# Sheet1.net
KiCad netlist of a schematic drawn in Altium Designer
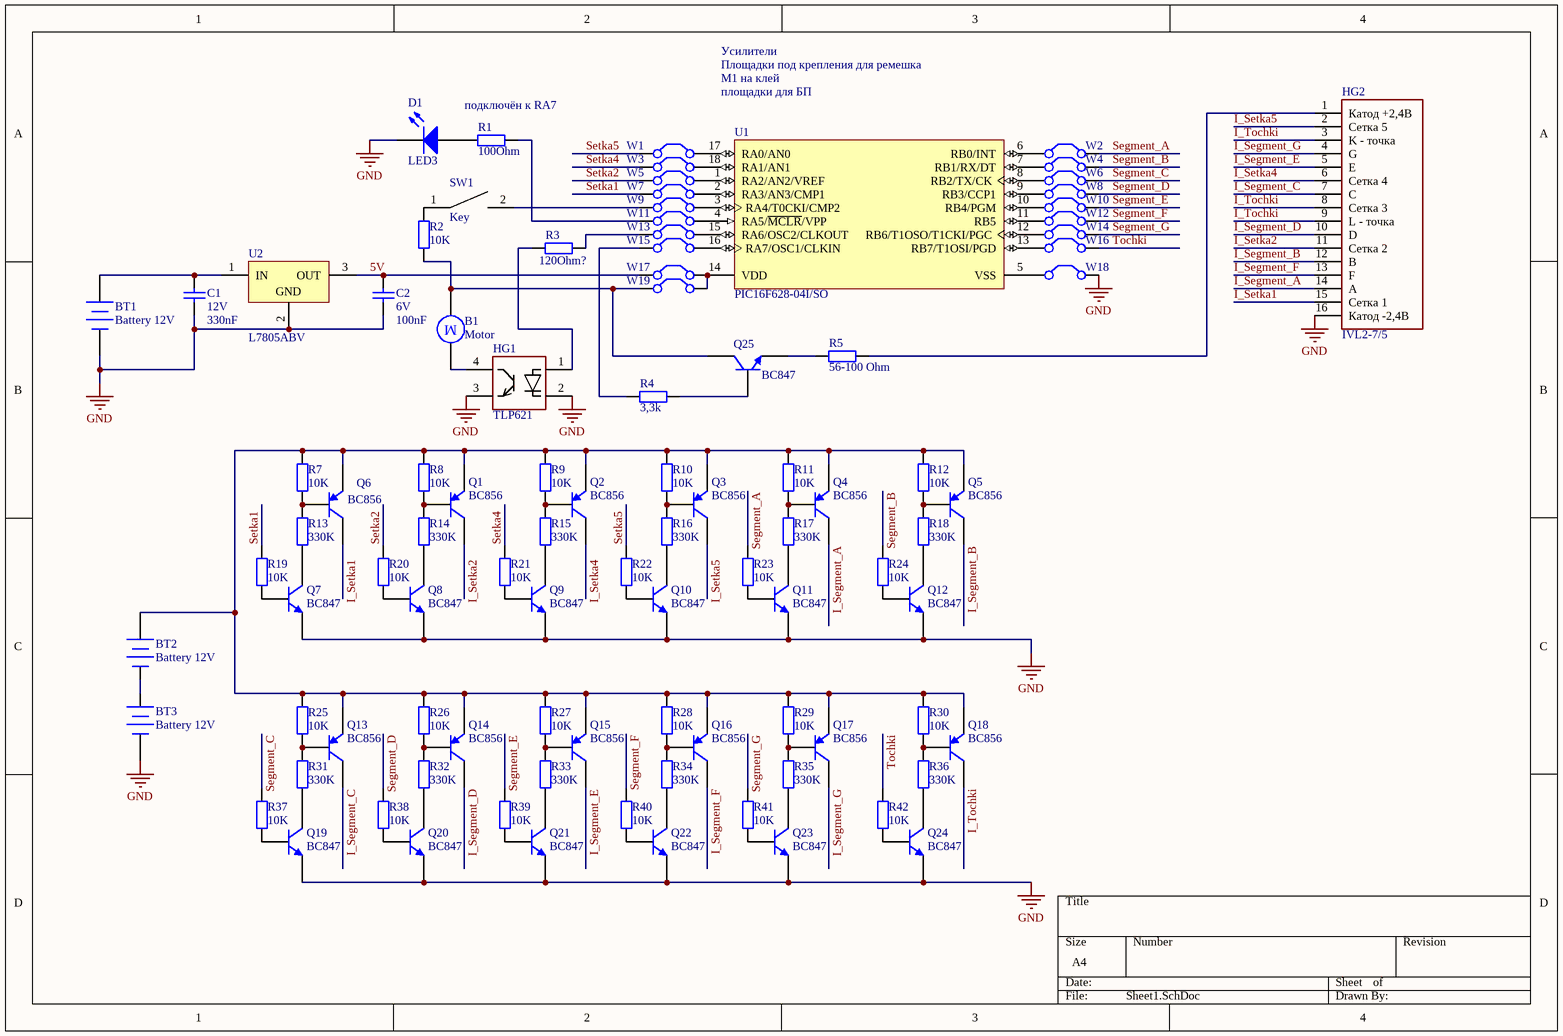
[diagram p0: Sheet1.SchDoc]

(export (version "E")
  (design (tool "Eeschema 10.0.6"))
  (components
    (comp (ref "B1")
      (value "Motor")
      (footprint "Motor")
      (description "Motor, General Kind")
      (fields (field (name "PUBLISHER") "Altium Limited"))
      (libsource (lib "Miscellaneous Devices") (part "Motor"))
    )
    (comp (ref "BT1")
      (value "Battery 12V")
      (footprint "BatteryA23")
      (description "Multicell Battery")
      (fields (field (name "PUBLISHER") "Altium Limited"))
      (libsource (lib "Miscellaneous Devices") (part "Battery"))
    )
    (comp (ref "BT2")
      (value "Battery 12V")
      (footprint "BatteryA23")
      (description "Multicell Battery")
      (fields (field (name "PUBLISHER") "Altium Limited"))
      (libsource (lib "Miscellaneous Devices") (part "Battery"))
    )
    (comp (ref "BT3")
      (value "Battery 12V")
      (footprint "PcbLib1:BatteryA23")
      (description "Multicell Battery")
      (fields (field (name "PUBLISHER") "Altium Limited"))
      (libsource (lib "Miscellaneous Devices") (part "Battery"))
    )
    (comp (ref "C1")
      (value "12V")
      (footprint "F1206")
      (description "Capacitor")
      (fields (field (name "ALTIUM_VALUE") "330nF") (field (name "PUBLISHER") "Altium Limited"))
      (libsource (lib "Miscellaneous Devices") (part "Cap"))
    )
    (comp (ref "C2")
      (value "6V")
      (footprint "F1206")
      (description "Capacitor")
      (fields (field (name "ALTIUM_VALUE") "100nF") (field (name "PUBLISHER") "Altium Limited"))
      (libsource (lib "Miscellaneous Devices") (part "Cap"))
    )
    (comp (ref "D1")
      (value "LED3")
      (footprint "F1206")
      (description "Typical BLUE SiC LED")
      (fields (field (name "PUBLISHER") "Altium Limited"))
      (libsource (lib "Miscellaneous Devices") (part "LED3"))
    )
    (comp (ref "HG1")
      (value "TLP621")
      (footprint "PcbLib1:Photocoupler")
      (libsource (lib "Schlib1") (part "Photocoupler"))
    )
    (comp (ref "HG2")
      (value "IVL2-7/5")
      (footprint "-IVL2-7/5")
      (libsource (lib "Schlib1") (part "IVL2-7/5"))
    )
    (comp (ref "Q1")
      (value "BC856")
      (footprint "SOT23_L")
      (description "PNP General-purpose Transistor")
      (fields (field (name "PUBLISHER") "Altium Limited"))
      (libsource (lib "Philips Discrete BJT - Low Power") (part "BC856"))
    )
    (comp (ref "Q2")
      (value "BC856")
      (footprint "SOT23_L")
      (description "PNP General-purpose Transistor")
      (fields (field (name "PUBLISHER") "Altium Limited"))
      (libsource (lib "Philips Discrete BJT - Low Power") (part "BC856"))
    )
    (comp (ref "Q3")
      (value "BC856")
      (footprint "SOT23_L")
      (description "PNP General-purpose Transistor")
      (fields (field (name "PUBLISHER") "Altium Limited"))
      (libsource (lib "Philips Discrete BJT - Low Power") (part "BC856"))
    )
    (comp (ref "Q4")
      (value "BC856")
      (footprint "SOT23_L")
      (description "PNP General-purpose Transistor")
      (fields (field (name "PUBLISHER") "Altium Limited"))
      (libsource (lib "Philips Discrete BJT - Low Power") (part "BC856"))
    )
    (comp (ref "Q5")
      (value "BC856")
      (footprint "SOT23_L")
      (description "PNP General-purpose Transistor")
      (fields (field (name "PUBLISHER") "Altium Limited"))
      (libsource (lib "Philips Discrete BJT - Low Power") (part "BC856"))
    )
    (comp (ref "Q6")
      (value "BC856")
      (footprint "SOT23_L")
      (description "PNP General-purpose Transistor")
      (fields (field (name "PUBLISHER") "Altium Limited"))
      (libsource (lib "Philips Discrete BJT - Low Power") (part "BC856"))
    )
    (comp (ref "Q7")
      (value "BC847")
      (footprint "SOT23_N")
      (description "NPN General-purpose Transistor")
      (fields (field (name "PUBLISHER") "Altium Limited"))
      (libsource (lib "Philips Discrete BJT - Low Power") (part "BC847"))
    )
    (comp (ref "Q8")
      (value "BC847")
      (footprint "SOT23_N")
      (description "NPN General-purpose Transistor")
      (fields (field (name "PUBLISHER") "Altium Limited"))
      (libsource (lib "Philips Discrete BJT - Low Power") (part "BC847"))
    )
    (comp (ref "Q9")
      (value "BC847")
      (footprint "SOT23_N")
      (description "NPN General-purpose Transistor")
      (fields (field (name "PUBLISHER") "Altium Limited"))
      (libsource (lib "Philips Discrete BJT - Low Power") (part "BC847"))
    )
    (comp (ref "Q10")
      (value "BC847")
      (footprint "SOT23_N")
      (description "NPN General-purpose Transistor")
      (fields (field (name "PUBLISHER") "Altium Limited"))
      (libsource (lib "Philips Discrete BJT - Low Power") (part "BC847"))
    )
    (comp (ref "Q11")
      (value "BC847")
      (footprint "SOT23_N")
      (description "NPN General-purpose Transistor")
      (fields (field (name "PUBLISHER") "Altium Limited"))
      (libsource (lib "Philips Discrete BJT - Low Power") (part "BC847"))
    )
    (comp (ref "Q12")
      (value "BC847")
      (footprint "SOT23_N")
      (description "NPN General-purpose Transistor")
      (fields (field (name "PUBLISHER") "Altium Limited"))
      (libsource (lib "Philips Discrete BJT - Low Power") (part "BC847"))
    )
    (comp (ref "Q13")
      (value "BC856")
      (footprint "SOT23_L")
      (description "PNP General-purpose Transistor")
      (fields (field (name "PUBLISHER") "Altium Limited"))
      (libsource (lib "Philips Discrete BJT - Low Power") (part "BC856"))
    )
    (comp (ref "Q14")
      (value "BC856")
      (footprint "SOT23_L")
      (description "PNP General-purpose Transistor")
      (fields (field (name "PUBLISHER") "Altium Limited"))
      (libsource (lib "Philips Discrete BJT - Low Power") (part "BC856"))
    )
    (comp (ref "Q15")
      (value "BC856")
      (footprint "SOT23_L")
      (description "PNP General-purpose Transistor")
      (fields (field (name "PUBLISHER") "Altium Limited"))
      (libsource (lib "Philips Discrete BJT - Low Power") (part "BC856"))
    )
    (comp (ref "Q16")
      (value "BC856")
      (footprint "SOT23_L")
      (description "PNP General-purpose Transistor")
      (fields (field (name "PUBLISHER") "Altium Limited"))
      (libsource (lib "Philips Discrete BJT - Low Power") (part "BC856"))
    )
    (comp (ref "Q17")
      (value "BC856")
      (footprint "SOT23_L")
      (description "PNP General-purpose Transistor")
      (fields (field (name "PUBLISHER") "Altium Limited"))
      (libsource (lib "Philips Discrete BJT - Low Power") (part "BC856"))
    )
    (comp (ref "Q18")
      (value "BC856")
      (footprint "SOT23_L")
      (description "PNP General-purpose Transistor")
      (fields (field (name "PUBLISHER") "Altium Limited"))
      (libsource (lib "Philips Discrete BJT - Low Power") (part "BC856"))
    )
    (comp (ref "Q19")
      (value "BC847")
      (footprint "SOT23_N")
      (description "NPN General-purpose Transistor")
      (fields (field (name "PUBLISHER") "Altium Limited"))
      (libsource (lib "Philips Discrete BJT - Low Power") (part "BC847"))
    )
    (comp (ref "Q20")
      (value "BC847")
      (footprint "SOT23_N")
      (description "NPN General-purpose Transistor")
      (fields (field (name "PUBLISHER") "Altium Limited"))
      (libsource (lib "Philips Discrete BJT - Low Power") (part "BC847"))
    )
    (comp (ref "Q21")
      (value "BC847")
      (footprint "SOT23_N")
      (description "NPN General-purpose Transistor")
      (fields (field (name "PUBLISHER") "Altium Limited"))
      (libsource (lib "Philips Discrete BJT - Low Power") (part "BC847"))
    )
    (comp (ref "Q22")
      (value "BC847")
      (footprint "SOT23_N")
      (description "NPN General-purpose Transistor")
      (fields (field (name "PUBLISHER") "Altium Limited"))
      (libsource (lib "Philips Discrete BJT - Low Power") (part "BC847"))
    )
    (comp (ref "Q23")
      (value "BC847")
      (footprint "SOT23_N")
      (description "NPN General-purpose Transistor")
      (fields (field (name "PUBLISHER") "Altium Limited"))
      (libsource (lib "Philips Discrete BJT - Low Power") (part "BC847"))
    )
    (comp (ref "Q24")
      (value "BC847")
      (footprint "SOT23_N")
      (description "NPN General-purpose Transistor")
      (fields (field (name "PUBLISHER") "Altium Limited"))
      (libsource (lib "Philips Discrete BJT - Low Power") (part "BC847"))
    )
    (comp (ref "Q25")
      (value "BC847")
      (footprint "SOT23_N")
      (description "NPN General-purpose Transistor")
      (fields (field (name "PUBLISHER") "Altium Limited"))
      (libsource (lib "Philips Discrete BJT - Low Power") (part "BC847"))
    )
    (comp (ref "R1")
      (value "100Ohm")
      (footprint "F1206")
      (description "Resistor")
      (fields (field (name "Comment") "Res2") (field (name "PUBLISHER") "Altium Limited"))
      (libsource (lib "") (part "Res2_3"))
    )
    (comp (ref "R2")
      (value "10K")
      (footprint "F1206")
      (description "Resistor")
      (fields (field (name "Comment") "Res2") (field (name "PUBLISHER") "Altium Limited"))
      (libsource (lib "Miscellaneous Devices") (part "Res2"))
    )
    (comp (ref "R3")
      (value "120Ohm?")
      (footprint "F1206")
      (description "Resistor")
      (fields (field (name "Comment") "Res2") (field (name "PUBLISHER") "Altium Limited"))
      (libsource (lib "") (part "Res2_3"))
    )
    (comp (ref "R4")
      (value "3,3k")
      (footprint "F1206")
      (description "Resistor")
      (fields (field (name "Comment") "Res2") (field (name "PUBLISHER") "Altium Limited"))
      (libsource (lib "") (part "Res2_3"))
    )
    (comp (ref "R5")
      (value "56-100 Ohm")
      (footprint "F1206")
      (description "Resistor")
      (fields (field (name "Comment") "Res2") (field (name "PUBLISHER") "Altium Limited"))
      (libsource (lib "") (part "Res2_2"))
    )
    (comp (ref "R7")
      (value "10K")
      (footprint "F0805")
      (description "Resistor")
      (fields (field (name "Comment") "Res2") (field (name "PUBLISHER") "Altium Limited"))
      (libsource (lib "Miscellaneous Devices") (part "Res2"))
    )
    (comp (ref "R8")
      (value "10K")
      (footprint "F0805")
      (description "Resistor")
      (fields (field (name "Comment") "Res2") (field (name "PUBLISHER") "Altium Limited"))
      (libsource (lib "Miscellaneous Devices") (part "Res2"))
    )
    (comp (ref "R9")
      (value "10K")
      (footprint "F0805")
      (description "Resistor")
      (fields (field (name "Comment") "Res2") (field (name "PUBLISHER") "Altium Limited"))
      (libsource (lib "Miscellaneous Devices") (part "Res2"))
    )
    (comp (ref "R10")
      (value "10K")
      (footprint "F0805")
      (description "Resistor")
      (fields (field (name "Comment") "Res2") (field (name "PUBLISHER") "Altium Limited"))
      (libsource (lib "Miscellaneous Devices") (part "Res2"))
    )
    (comp (ref "R11")
      (value "10K")
      (footprint "F0805")
      (description "Resistor")
      (fields (field (name "Comment") "Res2") (field (name "PUBLISHER") "Altium Limited"))
      (libsource (lib "Miscellaneous Devices") (part "Res2"))
    )
    (comp (ref "R12")
      (value "10K")
      (footprint "F0805")
      (description "Resistor")
      (fields (field (name "Comment") "Res2") (field (name "PUBLISHER") "Altium Limited"))
      (libsource (lib "Miscellaneous Devices") (part "Res2"))
    )
    (comp (ref "R13")
      (value "330K")
      (footprint "F1206")
      (description "Resistor")
      (fields (field (name "Comment") "Res2") (field (name "PUBLISHER") "Altium Limited"))
      (libsource (lib "Miscellaneous Devices") (part "Res2"))
    )
    (comp (ref "R14")
      (value "330K")
      (footprint "F1206")
      (description "Resistor")
      (fields (field (name "Comment") "Res2") (field (name "PUBLISHER") "Altium Limited"))
      (libsource (lib "Miscellaneous Devices") (part "Res2"))
    )
    (comp (ref "R15")
      (value "330K")
      (footprint "F1206")
      (description "Resistor")
      (fields (field (name "Comment") "Res2") (field (name "PUBLISHER") "Altium Limited"))
      (libsource (lib "Miscellaneous Devices") (part "Res2"))
    )
    (comp (ref "R16")
      (value "330K")
      (footprint "F1206")
      (description "Resistor")
      (fields (field (name "Comment") "Res2") (field (name "PUBLISHER") "Altium Limited"))
      (libsource (lib "Miscellaneous Devices") (part "Res2"))
    )
    (comp (ref "R17")
      (value "330K")
      (footprint "F1206")
      (description "Resistor")
      (fields (field (name "Comment") "Res2") (field (name "PUBLISHER") "Altium Limited"))
      (libsource (lib "Miscellaneous Devices") (part "Res2"))
    )
    (comp (ref "R18")
      (value "330K")
      (footprint "F1206")
      (description "Resistor")
      (fields (field (name "Comment") "Res2") (field (name "PUBLISHER") "Altium Limited"))
      (libsource (lib "Miscellaneous Devices") (part "Res2"))
    )
    (comp (ref "R19")
      (value "10K")
      (footprint "F1206")
      (description "Resistor")
      (fields (field (name "Comment") "Res2") (field (name "PUBLISHER") "Altium Limited"))
      (libsource (lib "") (part "Res2_1"))
    )
    (comp (ref "R20")
      (value "10K")
      (footprint "F1206")
      (description "Resistor")
      (fields (field (name "Comment") "Res2") (field (name "PUBLISHER") "Altium Limited"))
      (libsource (lib "") (part "Res2_1"))
    )
    (comp (ref "R21")
      (value "10K")
      (footprint "F1206")
      (description "Resistor")
      (fields (field (name "Comment") "Res2") (field (name "PUBLISHER") "Altium Limited"))
      (libsource (lib "") (part "Res2_1"))
    )
    (comp (ref "R22")
      (value "10K")
      (footprint "F1206")
      (description "Resistor")
      (fields (field (name "Comment") "Res2") (field (name "PUBLISHER") "Altium Limited"))
      (libsource (lib "") (part "Res2_1"))
    )
    (comp (ref "R23")
      (value "10K")
      (footprint "F1206")
      (description "Resistor")
      (fields (field (name "Comment") "Res2") (field (name "PUBLISHER") "Altium Limited"))
      (libsource (lib "") (part "Res2_1"))
    )
    (comp (ref "R24")
      (value "10K")
      (footprint "F1206")
      (description "Resistor")
      (fields (field (name "Comment") "Res2") (field (name "PUBLISHER") "Altium Limited"))
      (libsource (lib "") (part "Res2_1"))
    )
    (comp (ref "R25")
      (value "10K")
      (footprint "F0805")
      (description "Resistor")
      (fields (field (name "Comment") "Res2") (field (name "PUBLISHER") "Altium Limited"))
      (libsource (lib "Miscellaneous Devices") (part "Res2"))
    )
    (comp (ref "R26")
      (value "10K")
      (footprint "F0805")
      (description "Resistor")
      (fields (field (name "Comment") "Res2") (field (name "PUBLISHER") "Altium Limited"))
      (libsource (lib "Miscellaneous Devices") (part "Res2"))
    )
    (comp (ref "R27")
      (value "10K")
      (footprint "F0805")
      (description "Resistor")
      (fields (field (name "Comment") "Res2") (field (name "PUBLISHER") "Altium Limited"))
      (libsource (lib "Miscellaneous Devices") (part "Res2"))
    )
    (comp (ref "R28")
      (value "10K")
      (footprint "F0805")
      (description "Resistor")
      (fields (field (name "Comment") "Res2") (field (name "PUBLISHER") "Altium Limited"))
      (libsource (lib "Miscellaneous Devices") (part "Res2"))
    )
    (comp (ref "R29")
      (value "10K")
      (footprint "F0805")
      (description "Resistor")
      (fields (field (name "Comment") "Res2") (field (name "PUBLISHER") "Altium Limited"))
      (libsource (lib "Miscellaneous Devices") (part "Res2"))
    )
    (comp (ref "R30")
      (value "10K")
      (footprint "F0805")
      (description "Resistor")
      (fields (field (name "Comment") "Res2") (field (name "PUBLISHER") "Altium Limited"))
      (libsource (lib "Miscellaneous Devices") (part "Res2"))
    )
    (comp (ref "R31")
      (value "330K")
      (footprint "F1206")
      (description "Resistor")
      (fields (field (name "Comment") "Res2") (field (name "PUBLISHER") "Altium Limited"))
      (libsource (lib "Miscellaneous Devices") (part "Res2"))
    )
    (comp (ref "R32")
      (value "330K")
      (footprint "F1206")
      (description "Resistor")
      (fields (field (name "Comment") "Res2") (field (name "PUBLISHER") "Altium Limited"))
      (libsource (lib "Miscellaneous Devices") (part "Res2"))
    )
    (comp (ref "R33")
      (value "330K")
      (footprint "F1206")
      (description "Resistor")
      (fields (field (name "Comment") "Res2") (field (name "PUBLISHER") "Altium Limited"))
      (libsource (lib "Miscellaneous Devices") (part "Res2"))
    )
    (comp (ref "R34")
      (value "330K")
      (footprint "F1206")
      (description "Resistor")
      (fields (field (name "Comment") "Res2") (field (name "PUBLISHER") "Altium Limited"))
      (libsource (lib "Miscellaneous Devices") (part "Res2"))
    )
    (comp (ref "R35")
      (value "330K")
      (footprint "F1206")
      (description "Resistor")
      (fields (field (name "Comment") "Res2") (field (name "PUBLISHER") "Altium Limited"))
      (libsource (lib "Miscellaneous Devices") (part "Res2"))
    )
    (comp (ref "R36")
      (value "330K")
      (footprint "F1206")
      (description "Resistor")
      (fields (field (name "Comment") "Res2") (field (name "PUBLISHER") "Altium Limited"))
      (libsource (lib "Miscellaneous Devices") (part "Res2"))
    )
    (comp (ref "R37")
      (value "10K")
      (footprint "F1206")
      (description "Resistor")
      (fields (field (name "Comment") "Res2") (field (name "PUBLISHER") "Altium Limited"))
      (libsource (lib "") (part "Res2_1"))
    )
    (comp (ref "R38")
      (value "10K")
      (footprint "F1206")
      (description "Resistor")
      (fields (field (name "Comment") "Res2") (field (name "PUBLISHER") "Altium Limited"))
      (libsource (lib "") (part "Res2_1"))
    )
    (comp (ref "R39")
      (value "10K")
      (footprint "F1206")
      (description "Resistor")
      (fields (field (name "Comment") "Res2") (field (name "PUBLISHER") "Altium Limited"))
      (libsource (lib "") (part "Res2_1"))
    )
    (comp (ref "R40")
      (value "10K")
      (footprint "F1206")
      (description "Resistor")
      (fields (field (name "Comment") "Res2") (field (name "PUBLISHER") "Altium Limited"))
      (libsource (lib "") (part "Res2_1"))
    )
    (comp (ref "R41")
      (value "10K")
      (footprint "F1206")
      (description "Resistor")
      (fields (field (name "Comment") "Res2") (field (name "PUBLISHER") "Altium Limited"))
      (libsource (lib "") (part "Res2_1"))
    )
    (comp (ref "R42")
      (value "10K")
      (footprint "F1206")
      (description "Resistor")
      (fields (field (name "Comment") "Res2") (field (name "PUBLISHER") "Altium Limited"))
      (libsource (lib "") (part "Res2_1"))
    )
    (comp (ref "SW1") (value "Key") (footprint "Button") (libsource (lib "Schlib1") (part "SW")))
    (comp (ref "U1")
      (value "PIC16F628-04I/SO")
      (footprint "MCHP-SOIC-SO18_N")
      (description "Flash-Based 8-Bit CMOS Microcontroller, 4 MHz, 16 I/O, -40 to 85 degC, 18-pin SOIC (SO18), Tube")
      (fields (field (name "MANUFACTURER") "Microchip"))
      (libsource (lib "Microchip PIC16 Part 1") (part "PIC16F628-04I/SO"))
    )
    (comp (ref "U2")
      (value "L7805ABV")
      (footprint "KREN")
      (description "Positive Voltage Regulator, 5V, 3-Pin TO-220")
      (libsource (lib "STMicroelectronics Power Management Linear Regulator") (part "L7805ABV"))
    )
    (comp (ref "W1")
      (value "Jumper")
      (footprint "перемычка")
      (description "Jumper Wire")
      (fields (field (name "PUBLISHER") "Altium Limited"))
      (libsource (lib "Miscellaneous Devices") (part "Jumper"))
    )
    (comp (ref "W2")
      (value "Jumper")
      (footprint "перемычка")
      (description "Jumper Wire")
      (fields (field (name "PUBLISHER") "Altium Limited"))
      (libsource (lib "Miscellaneous Devices") (part "Jumper"))
    )
    (comp (ref "W3")
      (value "Jumper")
      (footprint "перемычка")
      (description "Jumper Wire")
      (fields (field (name "PUBLISHER") "Altium Limited"))
      (libsource (lib "Miscellaneous Devices") (part "Jumper"))
    )
    (comp (ref "W4")
      (value "Jumper")
      (footprint "перемычка")
      (description "Jumper Wire")
      (fields (field (name "PUBLISHER") "Altium Limited"))
      (libsource (lib "Miscellaneous Devices") (part "Jumper"))
    )
    (comp (ref "W5")
      (value "Jumper")
      (footprint "перемычка")
      (description "Jumper Wire")
      (fields (field (name "PUBLISHER") "Altium Limited"))
      (libsource (lib "Miscellaneous Devices") (part "Jumper"))
    )
    (comp (ref "W6")
      (value "Jumper")
      (footprint "перемычка")
      (description "Jumper Wire")
      (fields (field (name "PUBLISHER") "Altium Limited"))
      (libsource (lib "Miscellaneous Devices") (part "Jumper"))
    )
    (comp (ref "W7")
      (value "Jumper")
      (footprint "перемычка")
      (description "Jumper Wire")
      (fields (field (name "PUBLISHER") "Altium Limited"))
      (libsource (lib "Miscellaneous Devices") (part "Jumper"))
    )
    (comp (ref "W8")
      (value "Jumper")
      (footprint "перемычка")
      (description "Jumper Wire")
      (fields (field (name "PUBLISHER") "Altium Limited"))
      (libsource (lib "Miscellaneous Devices") (part "Jumper"))
    )
    (comp (ref "W9")
      (value "Jumper")
      (footprint "перемычка")
      (description "Jumper Wire")
      (fields (field (name "PUBLISHER") "Altium Limited"))
      (libsource (lib "Miscellaneous Devices") (part "Jumper"))
    )
    (comp (ref "W10")
      (value "Jumper")
      (footprint "перемычка")
      (description "Jumper Wire")
      (fields (field (name "PUBLISHER") "Altium Limited"))
      (libsource (lib "Miscellaneous Devices") (part "Jumper"))
    )
    (comp (ref "W11")
      (value "Jumper")
      (footprint "перемычка")
      (description "Jumper Wire")
      (fields (field (name "PUBLISHER") "Altium Limited"))
      (libsource (lib "Miscellaneous Devices") (part "Jumper"))
    )
    (comp (ref "W12")
      (value "Jumper")
      (footprint "перемычка")
      (description "Jumper Wire")
      (fields (field (name "PUBLISHER") "Altium Limited"))
      (libsource (lib "Miscellaneous Devices") (part "Jumper"))
    )
    (comp (ref "W13")
      (value "Jumper")
      (footprint "перемычка")
      (description "Jumper Wire")
      (fields (field (name "PUBLISHER") "Altium Limited"))
      (libsource (lib "Miscellaneous Devices") (part "Jumper"))
    )
    (comp (ref "W14")
      (value "Jumper")
      (footprint "перемычка")
      (description "Jumper Wire")
      (fields (field (name "PUBLISHER") "Altium Limited"))
      (libsource (lib "Miscellaneous Devices") (part "Jumper"))
    )
    (comp (ref "W15")
      (value "Jumper")
      (footprint "перемычка")
      (description "Jumper Wire")
      (fields (field (name "PUBLISHER") "Altium Limited"))
      (libsource (lib "Miscellaneous Devices") (part "Jumper"))
    )
    (comp (ref "W16")
      (value "Jumper")
      (footprint "перемычка")
      (description "Jumper Wire")
      (fields (field (name "PUBLISHER") "Altium Limited"))
      (libsource (lib "Miscellaneous Devices") (part "Jumper"))
    )
    (comp (ref "W17")
      (value "Jumper")
      (footprint "перемычка")
      (description "Jumper Wire")
      (fields (field (name "PUBLISHER") "Altium Limited"))
      (libsource (lib "Miscellaneous Devices") (part "Jumper"))
    )
    (comp (ref "W18")
      (value "Jumper")
      (footprint "перемычка")
      (description "Jumper Wire")
      (fields (field (name "PUBLISHER") "Altium Limited"))
      (libsource (lib "Miscellaneous Devices") (part "Jumper"))
    )
    (comp (ref "W19")
      (value "Jumper")
      (footprint "перемычка")
      (description "Jumper Wire")
      (fields (field (name "PUBLISHER") "Altium Limited"))
      (libsource (lib "Miscellaneous Devices") (part "Jumper"))
    )
  )
  (nets
    (net (code "1") (name "/5V") (class "Default")
      (node (ref "C2") (pin "1") (pinfunction "1_1") (pintype "passive"))
      (node (ref "U2") (pin "3") (pinfunction "OUT_3") (pintype "power_in"))
      (node (ref "W17") (pin "1") (pinfunction "C1_1") (pintype "passive"))
    )
    (net (code "2") (name "/I_Segment_A") (class "Default")
      (node (ref "HG2") (pin "14") (pinfunction "A_14") (pintype "passive"))
      (node (ref "Q4") (pin "3") (pinfunction "C_3") (pintype "passive"))
    )
    (net (code "3") (name "/I_Segment_B") (class "Default")
      (node (ref "HG2") (pin "12") (pinfunction "B_12") (pintype "passive"))
      (node (ref "Q5") (pin "3") (pinfunction "C_3") (pintype "passive"))
    )
    (net (code "4") (name "/I_Segment_C") (class "Default")
      (node (ref "HG2") (pin "7") (pinfunction "C_7") (pintype "passive"))
      (node (ref "Q13") (pin "3") (pinfunction "C_3") (pintype "passive"))
    )
    (net (code "5") (name "/I_Segment_D") (class "Default")
      (node (ref "HG2") (pin "10") (pinfunction "D_10") (pintype "passive"))
      (node (ref "Q14") (pin "3") (pinfunction "C_3") (pintype "passive"))
    )
    (net (code "6") (name "/I_Segment_E") (class "Default")
      (node (ref "HG2") (pin "5") (pinfunction "E_5") (pintype "passive"))
      (node (ref "Q15") (pin "3") (pinfunction "C_3") (pintype "passive"))
    )
    (net (code "7") (name "/I_Segment_F") (class "Default")
      (node (ref "HG2") (pin "13") (pinfunction "F_13") (pintype "passive"))
      (node (ref "Q16") (pin "3") (pinfunction "C_3") (pintype "passive"))
    )
    (net (code "8") (name "/I_Segment_G") (class "Default")
      (node (ref "HG2") (pin "4") (pinfunction "G_4") (pintype "passive"))
      (node (ref "Q17") (pin "3") (pinfunction "C_3") (pintype "passive"))
    )
    (net (code "9") (name "/I_Setka1") (class "Default")
      (node (ref "HG2") (pin "15") (pinfunction "Сетка_1_15") (pintype "passive"))
      (node (ref "Q6") (pin "3") (pinfunction "C_3") (pintype "passive"))
    )
    (net (code "10") (name "/I_Setka2") (class "Default")
      (node (ref "HG2") (pin "11") (pinfunction "Сетка_2_11") (pintype "passive"))
      (node (ref "Q1") (pin "3") (pinfunction "C_3") (pintype "passive"))
    )
    (net (code "11") (name "/I_Setka4") (class "Default")
      (node (ref "HG2") (pin "6") (pinfunction "Сетка_4_6") (pintype "passive"))
      (node (ref "Q2") (pin "3") (pinfunction "C_3") (pintype "passive"))
    )
    (net (code "12") (name "/I_Setka5") (class "Default")
      (node (ref "HG2") (pin "2") (pinfunction "Сетка_5_2") (pintype "passive"))
      (node (ref "Q3") (pin "3") (pinfunction "C_3") (pintype "passive"))
    )
    (net (code "13") (name "/I_Tochki") (class "Default")
      (node (ref "HG2") (pin "3") (pinfunction "K_-_точка_3") (pintype "passive"))
      (node (ref "HG2") (pin "8") (pinfunction "Сетка_3_8") (pintype "passive"))
      (node (ref "HG2") (pin "9") (pinfunction "L_-_точка_9") (pintype "passive"))
      (node (ref "Q18") (pin "3") (pinfunction "C_3") (pintype "passive"))
    )
    (net (code "14") (name "/Segment_A") (class "Default")
      (node (ref "R23") (pin "1") (pinfunction "1_1") (pintype "passive"))
      (node (ref "W2") (pin "2") (pinfunction "C2_2") (pintype "passive"))
    )
    (net (code "15") (name "/Segment_B") (class "Default")
      (node (ref "R24") (pin "1") (pinfunction "1_1") (pintype "passive"))
      (node (ref "W4") (pin "2") (pinfunction "C2_2") (pintype "passive"))
    )
    (net (code "16") (name "/Segment_C") (class "Default")
      (node (ref "R37") (pin "1") (pinfunction "1_1") (pintype "passive"))
      (node (ref "W6") (pin "2") (pinfunction "C2_2") (pintype "passive"))
    )
    (net (code "17") (name "/Segment_D") (class "Default")
      (node (ref "R38") (pin "1") (pinfunction "1_1") (pintype "passive"))
      (node (ref "W8") (pin "2") (pinfunction "C2_2") (pintype "passive"))
    )
    (net (code "18") (name "/Segment_E") (class "Default")
      (node (ref "R39") (pin "1") (pinfunction "1_1") (pintype "passive"))
      (node (ref "W10") (pin "2") (pinfunction "C2_2") (pintype "passive"))
    )
    (net (code "19") (name "/Segment_F") (class "Default")
      (node (ref "R40") (pin "1") (pinfunction "1_1") (pintype "passive"))
      (node (ref "W12") (pin "2") (pinfunction "C2_2") (pintype "passive"))
    )
    (net (code "20") (name "/Segment_G") (class "Default")
      (node (ref "R41") (pin "1") (pinfunction "1_1") (pintype "passive"))
      (node (ref "W14") (pin "2") (pinfunction "C2_2") (pintype "passive"))
    )
    (net (code "21") (name "/Setka1") (class "Default")
      (node (ref "R19") (pin "1") (pinfunction "1_1") (pintype "passive"))
      (node (ref "W7") (pin "1") (pinfunction "C1_1") (pintype "passive"))
    )
    (net (code "22") (name "/Setka2") (class "Default")
      (node (ref "R20") (pin "1") (pinfunction "1_1") (pintype "passive"))
      (node (ref "W5") (pin "1") (pinfunction "C1_1") (pintype "passive"))
    )
    (net (code "23") (name "/Setka4") (class "Default")
      (node (ref "R21") (pin "1") (pinfunction "1_1") (pintype "passive"))
      (node (ref "W3") (pin "1") (pinfunction "C1_1") (pintype "passive"))
    )
    (net (code "24") (name "/Setka5") (class "Default")
      (node (ref "R22") (pin "1") (pinfunction "1_1") (pintype "passive"))
      (node (ref "W1") (pin "1") (pinfunction "C1_1") (pintype "passive"))
    )
    (net (code "25") (name "/Tochki") (class "Default")
      (node (ref "R42") (pin "1") (pinfunction "1_1") (pintype "passive"))
      (node (ref "W16") (pin "2") (pinfunction "C2_2") (pintype "passive"))
    )
    (net (code "26") (name "GND") (class "Default")
      (node (ref "BT1") (pin "2") (pinfunction "-_2") (pintype "passive"))
      (node (ref "BT3") (pin "2") (pinfunction "-_2") (pintype "passive"))
      (node (ref "C1") (pin "1") (pinfunction "1_1") (pintype "passive"))
      (node (ref "C2") (pin "2") (pinfunction "2_2") (pintype "passive"))
      (node (ref "D1") (pin "2") (pinfunction "K_2") (pintype "passive"))
      (node (ref "HG1") (pin "2") (pinfunction "2_2") (pintype "passive"))
      (node (ref "HG1") (pin "3") (pinfunction "3_3") (pintype "passive"))
      (node (ref "HG2") (pin "16") (pinfunction "Катод_-2,4В_16") (pintype "passive"))
      (node (ref "Q10") (pin "2") (pinfunction "E_2") (pintype "passive"))
      (node (ref "Q11") (pin "2") (pinfunction "E_2") (pintype "passive"))
      (node (ref "Q12") (pin "2") (pinfunction "E_2") (pintype "passive"))
      (node (ref "Q19") (pin "2") (pinfunction "E_2") (pintype "passive"))
      (node (ref "Q20") (pin "2") (pinfunction "E_2") (pintype "passive"))
      (node (ref "Q21") (pin "2") (pinfunction "E_2") (pintype "passive"))
      (node (ref "Q22") (pin "2") (pinfunction "E_2") (pintype "passive"))
      (node (ref "Q23") (pin "2") (pinfunction "E_2") (pintype "passive"))
      (node (ref "Q24") (pin "2") (pinfunction "E_2") (pintype "passive"))
      (node (ref "Q7") (pin "2") (pinfunction "E_2") (pintype "passive"))
      (node (ref "Q8") (pin "2") (pinfunction "E_2") (pintype "passive"))
      (node (ref "Q9") (pin "2") (pinfunction "E_2") (pintype "passive"))
      (node (ref "U2") (pin "2") (pinfunction "GND_2") (pintype "power_in"))
      (node (ref "W18") (pin "2") (pinfunction "C2_2") (pintype "passive"))
    )
    (net (code "27") (name "Net-(B1-Pad1)") (class "Default")
      (node (ref "B1") (pin "1") (pinfunction "1_1") (pintype "passive"))
      (node (ref "HG1") (pin "4") (pinfunction "4_4") (pintype "passive"))
    )
    (net (code "28") (name "Net-(BT1-+)") (class "Default")
      (node (ref "BT1") (pin "1") (pinfunction "+_1") (pintype "passive"))
      (node (ref "C1") (pin "2") (pinfunction "2_2") (pintype "passive"))
      (node (ref "U2") (pin "1") (pinfunction "IN_1") (pintype "power_in"))
    )
    (net (code "29") (name "Net-(BT2-+)") (class "Default")
      (node (ref "BT2") (pin "1") (pinfunction "+_1") (pintype "passive"))
      (node (ref "Q1") (pin "2") (pinfunction "E_2") (pintype "passive"))
      (node (ref "Q13") (pin "2") (pinfunction "E_2") (pintype "passive"))
      (node (ref "Q14") (pin "2") (pinfunction "E_2") (pintype "passive"))
      (node (ref "Q15") (pin "2") (pinfunction "E_2") (pintype "passive"))
      (node (ref "Q16") (pin "2") (pinfunction "E_2") (pintype "passive"))
      (node (ref "Q17") (pin "2") (pinfunction "E_2") (pintype "passive"))
      (node (ref "Q18") (pin "2") (pinfunction "E_2") (pintype "passive"))
      (node (ref "Q2") (pin "2") (pinfunction "E_2") (pintype "passive"))
      (node (ref "Q3") (pin "2") (pinfunction "E_2") (pintype "passive"))
      (node (ref "Q4") (pin "2") (pinfunction "E_2") (pintype "passive"))
      (node (ref "Q5") (pin "2") (pinfunction "E_2") (pintype "passive"))
      (node (ref "Q6") (pin "2") (pinfunction "E_2") (pintype "passive"))
      (node (ref "R10") (pin "2") (pinfunction "2_2") (pintype "passive"))
      (node (ref "R11") (pin "2") (pinfunction "2_2") (pintype "passive"))
      (node (ref "R12") (pin "2") (pinfunction "2_2") (pintype "passive"))
      (node (ref "R25") (pin "2") (pinfunction "2_2") (pintype "passive"))
      (node (ref "R26") (pin "2") (pinfunction "2_2") (pintype "passive"))
      (node (ref "R27") (pin "2") (pinfunction "2_2") (pintype "passive"))
      (node (ref "R28") (pin "2") (pinfunction "2_2") (pintype "passive"))
      (node (ref "R29") (pin "2") (pinfunction "2_2") (pintype "passive"))
      (node (ref "R30") (pin "2") (pinfunction "2_2") (pintype "passive"))
      (node (ref "R7") (pin "2") (pinfunction "2_2") (pintype "passive"))
      (node (ref "R8") (pin "2") (pinfunction "2_2") (pintype "passive"))
      (node (ref "R9") (pin "2") (pinfunction "2_2") (pintype "passive"))
    )
    (net (code "30") (name "Net-(BT2--)") (class "Default")
      (node (ref "BT2") (pin "2") (pinfunction "-_2") (pintype "passive"))
      (node (ref "BT3") (pin "1") (pinfunction "+_1") (pintype "passive"))
    )
    (net (code "31") (name "Net-(D1-A)") (class "Default")
      (node (ref "D1") (pin "1") (pinfunction "A_1") (pintype "passive"))
      (node (ref "R1") (pin "1") (pinfunction "1_1") (pintype "passive"))
    )
    (net (code "32") (name "Net-(HG1-Pad1)") (class "Default")
      (node (ref "HG1") (pin "1") (pinfunction "1_1") (pintype "passive"))
      (node (ref "R3") (pin "1") (pinfunction "1_1") (pintype "passive"))
    )
    (net (code "33") (name "Net-(HG2-Катод_+2,4В)") (class "Default")
      (node (ref "HG2") (pin "1") (pinfunction "Катод_+2,4В_1") (pintype "passive"))
      (node (ref "R5") (pin "1") (pinfunction "1_1") (pintype "passive"))
    )
    (net (code "34") (name "Net-(Q1-B)") (class "Default")
      (node (ref "Q1") (pin "1") (pinfunction "B_1") (pintype "passive"))
      (node (ref "R14") (pin "2") (pinfunction "2_2") (pintype "passive"))
      (node (ref "R8") (pin "1") (pinfunction "1_1") (pintype "passive"))
    )
    (net (code "35") (name "Net-(Q2-B)") (class "Default")
      (node (ref "Q2") (pin "1") (pinfunction "B_1") (pintype "passive"))
      (node (ref "R15") (pin "2") (pinfunction "2_2") (pintype "passive"))
      (node (ref "R9") (pin "1") (pinfunction "1_1") (pintype "passive"))
    )
    (net (code "36") (name "Net-(Q3-B)") (class "Default")
      (node (ref "Q3") (pin "1") (pinfunction "B_1") (pintype "passive"))
      (node (ref "R10") (pin "1") (pinfunction "1_1") (pintype "passive"))
      (node (ref "R16") (pin "2") (pinfunction "2_2") (pintype "passive"))
    )
    (net (code "37") (name "Net-(Q4-B)") (class "Default")
      (node (ref "Q4") (pin "1") (pinfunction "B_1") (pintype "passive"))
      (node (ref "R11") (pin "1") (pinfunction "1_1") (pintype "passive"))
      (node (ref "R17") (pin "2") (pinfunction "2_2") (pintype "passive"))
    )
    (net (code "38") (name "Net-(Q5-B)") (class "Default")
      (node (ref "Q5") (pin "1") (pinfunction "B_1") (pintype "passive"))
      (node (ref "R12") (pin "1") (pinfunction "1_1") (pintype "passive"))
      (node (ref "R18") (pin "2") (pinfunction "2_2") (pintype "passive"))
    )
    (net (code "39") (name "Net-(Q6-B)") (class "Default")
      (node (ref "Q6") (pin "1") (pinfunction "B_1") (pintype "passive"))
      (node (ref "R13") (pin "2") (pinfunction "2_2") (pintype "passive"))
      (node (ref "R7") (pin "1") (pinfunction "1_1") (pintype "passive"))
    )
    (net (code "40") (name "Net-(Q7-B)") (class "Default")
      (node (ref "Q7") (pin "1") (pinfunction "B_1") (pintype "passive"))
      (node (ref "R19") (pin "2") (pinfunction "2_2") (pintype "passive"))
    )
    (net (code "41") (name "Net-(Q7-C)") (class "Default")
      (node (ref "Q7") (pin "3") (pinfunction "C_3") (pintype "passive"))
      (node (ref "R13") (pin "1") (pinfunction "1_1") (pintype "passive"))
    )
    (net (code "42") (name "Net-(Q8-B)") (class "Default")
      (node (ref "Q8") (pin "1") (pinfunction "B_1") (pintype "passive"))
      (node (ref "R20") (pin "2") (pinfunction "2_2") (pintype "passive"))
    )
    (net (code "43") (name "Net-(Q8-C)") (class "Default")
      (node (ref "Q8") (pin "3") (pinfunction "C_3") (pintype "passive"))
      (node (ref "R14") (pin "1") (pinfunction "1_1") (pintype "passive"))
    )
    (net (code "44") (name "Net-(Q9-B)") (class "Default")
      (node (ref "Q9") (pin "1") (pinfunction "B_1") (pintype "passive"))
      (node (ref "R21") (pin "2") (pinfunction "2_2") (pintype "passive"))
    )
    (net (code "45") (name "Net-(Q9-C)") (class "Default")
      (node (ref "Q9") (pin "3") (pinfunction "C_3") (pintype "passive"))
      (node (ref "R15") (pin "1") (pinfunction "1_1") (pintype "passive"))
    )
    (net (code "46") (name "Net-(Q10-B)") (class "Default")
      (node (ref "Q10") (pin "1") (pinfunction "B_1") (pintype "passive"))
      (node (ref "R22") (pin "2") (pinfunction "2_2") (pintype "passive"))
    )
    (net (code "47") (name "Net-(Q10-C)") (class "Default")
      (node (ref "Q10") (pin "3") (pinfunction "C_3") (pintype "passive"))
      (node (ref "R16") (pin "1") (pinfunction "1_1") (pintype "passive"))
    )
    (net (code "48") (name "Net-(Q11-B)") (class "Default")
      (node (ref "Q11") (pin "1") (pinfunction "B_1") (pintype "passive"))
      (node (ref "R23") (pin "2") (pinfunction "2_2") (pintype "passive"))
    )
    (net (code "49") (name "Net-(Q11-C)") (class "Default")
      (node (ref "Q11") (pin "3") (pinfunction "C_3") (pintype "passive"))
      (node (ref "R17") (pin "1") (pinfunction "1_1") (pintype "passive"))
    )
    (net (code "50") (name "Net-(Q12-B)") (class "Default")
      (node (ref "Q12") (pin "1") (pinfunction "B_1") (pintype "passive"))
      (node (ref "R24") (pin "2") (pinfunction "2_2") (pintype "passive"))
    )
    (net (code "51") (name "Net-(Q12-C)") (class "Default")
      (node (ref "Q12") (pin "3") (pinfunction "C_3") (pintype "passive"))
      (node (ref "R18") (pin "1") (pinfunction "1_1") (pintype "passive"))
    )
    (net (code "52") (name "Net-(Q13-B)") (class "Default")
      (node (ref "Q13") (pin "1") (pinfunction "B_1") (pintype "passive"))
      (node (ref "R25") (pin "1") (pinfunction "1_1") (pintype "passive"))
      (node (ref "R31") (pin "2") (pinfunction "2_2") (pintype "passive"))
    )
    (net (code "53") (name "Net-(Q14-B)") (class "Default")
      (node (ref "Q14") (pin "1") (pinfunction "B_1") (pintype "passive"))
      (node (ref "R26") (pin "1") (pinfunction "1_1") (pintype "passive"))
      (node (ref "R32") (pin "2") (pinfunction "2_2") (pintype "passive"))
    )
    (net (code "54") (name "Net-(Q15-B)") (class "Default")
      (node (ref "Q15") (pin "1") (pinfunction "B_1") (pintype "passive"))
      (node (ref "R27") (pin "1") (pinfunction "1_1") (pintype "passive"))
      (node (ref "R33") (pin "2") (pinfunction "2_2") (pintype "passive"))
    )
    (net (code "55") (name "Net-(Q16-B)") (class "Default")
      (node (ref "Q16") (pin "1") (pinfunction "B_1") (pintype "passive"))
      (node (ref "R28") (pin "1") (pinfunction "1_1") (pintype "passive"))
      (node (ref "R34") (pin "2") (pinfunction "2_2") (pintype "passive"))
    )
    (net (code "56") (name "Net-(Q17-B)") (class "Default")
      (node (ref "Q17") (pin "1") (pinfunction "B_1") (pintype "passive"))
      (node (ref "R29") (pin "1") (pinfunction "1_1") (pintype "passive"))
      (node (ref "R35") (pin "2") (pinfunction "2_2") (pintype "passive"))
    )
    (net (code "57") (name "Net-(Q18-B)") (class "Default")
      (node (ref "Q18") (pin "1") (pinfunction "B_1") (pintype "passive"))
      (node (ref "R30") (pin "1") (pinfunction "1_1") (pintype "passive"))
      (node (ref "R36") (pin "2") (pinfunction "2_2") (pintype "passive"))
    )
    (net (code "58") (name "Net-(Q19-B)") (class "Default")
      (node (ref "Q19") (pin "1") (pinfunction "B_1") (pintype "passive"))
      (node (ref "R37") (pin "2") (pinfunction "2_2") (pintype "passive"))
    )
    (net (code "59") (name "Net-(Q19-C)") (class "Default")
      (node (ref "Q19") (pin "3") (pinfunction "C_3") (pintype "passive"))
      (node (ref "R31") (pin "1") (pinfunction "1_1") (pintype "passive"))
    )
    (net (code "60") (name "Net-(Q20-B)") (class "Default")
      (node (ref "Q20") (pin "1") (pinfunction "B_1") (pintype "passive"))
      (node (ref "R38") (pin "2") (pinfunction "2_2") (pintype "passive"))
    )
    (net (code "61") (name "Net-(Q20-C)") (class "Default")
      (node (ref "Q20") (pin "3") (pinfunction "C_3") (pintype "passive"))
      (node (ref "R32") (pin "1") (pinfunction "1_1") (pintype "passive"))
    )
    (net (code "62") (name "Net-(Q21-B)") (class "Default")
      (node (ref "Q21") (pin "1") (pinfunction "B_1") (pintype "passive"))
      (node (ref "R39") (pin "2") (pinfunction "2_2") (pintype "passive"))
    )
    (net (code "63") (name "Net-(Q21-C)") (class "Default")
      (node (ref "Q21") (pin "3") (pinfunction "C_3") (pintype "passive"))
      (node (ref "R33") (pin "1") (pinfunction "1_1") (pintype "passive"))
    )
    (net (code "64") (name "Net-(Q22-B)") (class "Default")
      (node (ref "Q22") (pin "1") (pinfunction "B_1") (pintype "passive"))
      (node (ref "R40") (pin "2") (pinfunction "2_2") (pintype "passive"))
    )
    (net (code "65") (name "Net-(Q22-C)") (class "Default")
      (node (ref "Q22") (pin "3") (pinfunction "C_3") (pintype "passive"))
      (node (ref "R34") (pin "1") (pinfunction "1_1") (pintype "passive"))
    )
    (net (code "66") (name "Net-(Q23-B)") (class "Default")
      (node (ref "Q23") (pin "1") (pinfunction "B_1") (pintype "passive"))
      (node (ref "R41") (pin "2") (pinfunction "2_2") (pintype "passive"))
    )
    (net (code "67") (name "Net-(Q23-C)") (class "Default")
      (node (ref "Q23") (pin "3") (pinfunction "C_3") (pintype "passive"))
      (node (ref "R35") (pin "1") (pinfunction "1_1") (pintype "passive"))
    )
    (net (code "68") (name "Net-(Q24-B)") (class "Default")
      (node (ref "Q24") (pin "1") (pinfunction "B_1") (pintype "passive"))
      (node (ref "R42") (pin "2") (pinfunction "2_2") (pintype "passive"))
    )
    (net (code "69") (name "Net-(Q24-C)") (class "Default")
      (node (ref "Q24") (pin "3") (pinfunction "C_3") (pintype "passive"))
      (node (ref "R36") (pin "1") (pinfunction "1_1") (pintype "passive"))
    )
    (net (code "70") (name "Net-(Q25-B)") (class "Default")
      (node (ref "Q25") (pin "1") (pinfunction "B_1") (pintype "passive"))
      (node (ref "R4") (pin "2") (pinfunction "2_2") (pintype "passive"))
    )
    (net (code "71") (name "Net-(Q25-C)") (class "Default")
      (node (ref "B1") (pin "2") (pinfunction "2_2") (pintype "passive"))
      (node (ref "Q25") (pin "3") (pinfunction "C_3") (pintype "passive"))
      (node (ref "R2") (pin "1") (pinfunction "1_1") (pintype "passive"))
      (node (ref "W19") (pin "1") (pinfunction "C1_1") (pintype "passive"))
    )
    (net (code "72") (name "Net-(Q25-E)") (class "Default")
      (node (ref "Q25") (pin "2") (pinfunction "E_2") (pintype "passive"))
      (node (ref "R5") (pin "2") (pinfunction "2_2") (pintype "passive"))
    )
    (net (code "73") (name "Net-(R2-Pad2)") (class "Default")
      (node (ref "R2") (pin "2") (pinfunction "2_2") (pintype "passive"))
      (node (ref "SW1") (pin "1") (pinfunction "1_1") (pintype "passive"))
    )
    (net (code "74") (name "Net-(U1-RA0{slash}AN0)") (class "Default")
      (node (ref "U1") (pin "17") (pinfunction "RA0/AN0_17") (pintype "bidirectional"))
      (node (ref "W1") (pin "2") (pinfunction "C2_2") (pintype "passive"))
    )
    (net (code "75") (name "Net-(U1-RA1{slash}AN1)") (class "Default")
      (node (ref "U1") (pin "18") (pinfunction "RA1/AN1_18") (pintype "bidirectional"))
      (node (ref "W3") (pin "2") (pinfunction "C2_2") (pintype "passive"))
    )
    (net (code "76") (name "Net-(U1-RA2{slash}AN2{slash}VREF)") (class "Default")
      (node (ref "U1") (pin "1") (pinfunction "RA2/AN2/VREF_1") (pintype "bidirectional"))
      (node (ref "W5") (pin "2") (pinfunction "C2_2") (pintype "passive"))
    )
    (net (code "77") (name "Net-(U1-RA3{slash}AN3{slash}CMP1)") (class "Default")
      (node (ref "U1") (pin "2") (pinfunction "RA3/AN3/CMP1_2") (pintype "bidirectional"))
      (node (ref "W7") (pin "2") (pinfunction "C2_2") (pintype "passive"))
    )
    (net (code "78") (name "Net-(U1-RA4{slash}T0CKI{slash}CMP2)") (class "Default")
      (node (ref "U1") (pin "3") (pinfunction "RA4/T0CKI/CMP2_3") (pintype "bidirectional"))
      (node (ref "W9") (pin "2") (pinfunction "C2_2") (pintype "passive"))
    )
    (net (code "79") (name "Net-(U1-RA5{slash}~{MCLR}{slash}VPP)") (class "Default")
      (node (ref "U1") (pin "4") (pinfunction "RA5/~{MCLR}/VPP_4") (pintype "input"))
      (node (ref "W11") (pin "2") (pinfunction "C2_2") (pintype "passive"))
    )
    (net (code "80") (name "Net-(U1-RA6{slash}OSC2{slash}CLKOUT)") (class "Default")
      (node (ref "U1") (pin "15") (pinfunction "RA6/OSC2/CLKOUT_15") (pintype "bidirectional"))
      (node (ref "W13") (pin "2") (pinfunction "C2_2") (pintype "passive"))
    )
    (net (code "81") (name "Net-(U1-RA7{slash}OSC1{slash}CLKIN)") (class "Default")
      (node (ref "U1") (pin "16") (pinfunction "RA7/OSC1/CLKIN_16") (pintype "bidirectional"))
      (node (ref "W15") (pin "2") (pinfunction "C2_2") (pintype "passive"))
    )
    (net (code "82") (name "Net-(U1-RB0{slash}INT)") (class "Default")
      (node (ref "U1") (pin "6") (pinfunction "RB0/INT_6") (pintype "bidirectional"))
      (node (ref "W2") (pin "1") (pinfunction "C1_1") (pintype "passive"))
    )
    (net (code "83") (name "Net-(U1-RB1{slash}RX{slash}DT)") (class "Default")
      (node (ref "U1") (pin "7") (pinfunction "RB1/RX/DT_7") (pintype "bidirectional"))
      (node (ref "W4") (pin "1") (pinfunction "C1_1") (pintype "passive"))
    )
    (net (code "84") (name "Net-(U1-RB2{slash}TX{slash}CK)") (class "Default")
      (node (ref "U1") (pin "8") (pinfunction "RB2/TX/CK_8") (pintype "bidirectional"))
      (node (ref "W6") (pin "1") (pinfunction "C1_1") (pintype "passive"))
    )
    (net (code "85") (name "Net-(U1-RB3{slash}CCP1)") (class "Default")
      (node (ref "U1") (pin "9") (pinfunction "RB3/CCP1_9") (pintype "bidirectional"))
      (node (ref "W8") (pin "1") (pinfunction "C1_1") (pintype "passive"))
    )
    (net (code "86") (name "Net-(U1-RB4{slash}PGM)") (class "Default")
      (node (ref "U1") (pin "10") (pinfunction "RB4/PGM_10") (pintype "bidirectional"))
      (node (ref "W10") (pin "1") (pinfunction "C1_1") (pintype "passive"))
    )
    (net (code "87") (name "Net-(U1-RB5)") (class "Default")
      (node (ref "U1") (pin "11") (pinfunction "RB5_11") (pintype "bidirectional"))
      (node (ref "W12") (pin "1") (pinfunction "C1_1") (pintype "passive"))
    )
    (net (code "88") (name "Net-(U1-RB6{slash}T1OSO{slash}T1CKI{slash}PGC)") (class "Default")
      (node (ref "U1") (pin "12") (pinfunction "RB6/T1OSO/T1CKI/PGC_12") (pintype "bidirectional"))
      (node (ref "W14") (pin "1") (pinfunction "C1_1") (pintype "passive"))
    )
    (net (code "89") (name "Net-(U1-RB7{slash}T1OSI{slash}PGD)") (class "Default")
      (node (ref "U1") (pin "13") (pinfunction "RB7/T1OSI/PGD_13") (pintype "bidirectional"))
      (node (ref "W16") (pin "1") (pinfunction "C1_1") (pintype "passive"))
    )
    (net (code "90") (name "Net-(U1-VDD)") (class "Default")
      (node (ref "U1") (pin "14") (pinfunction "VDD_14") (pintype "power_in"))
      (node (ref "W17") (pin "2") (pinfunction "C2_2") (pintype "passive"))
      (node (ref "W19") (pin "2") (pinfunction "C2_2") (pintype "passive"))
    )
    (net (code "91") (name "Net-(U1-VSS)") (class "Default")
      (node (ref "U1") (pin "5") (pinfunction "VSS_5") (pintype "power_in"))
      (node (ref "W18") (pin "1") (pinfunction "C1_1") (pintype "passive"))
    )
    (net (code "92") (name "Net-(W9-C1)") (class "Default")
      (node (ref "SW1") (pin "2") (pinfunction "2_2") (pintype "passive"))
      (node (ref "W9") (pin "1") (pinfunction "C1_1") (pintype "passive"))
    )
    (net (code "93") (name "Net-(W11-C1)") (class "Default")
      (node (ref "R1") (pin "2") (pinfunction "2_2") (pintype "passive"))
      (node (ref "W11") (pin "1") (pinfunction "C1_1") (pintype "passive"))
    )
    (net (code "94") (name "Net-(W13-C1)") (class "Default")
      (node (ref "R3") (pin "2") (pinfunction "2_2") (pintype "passive"))
      (node (ref "W13") (pin "1") (pinfunction "C1_1") (pintype "passive"))
    )
    (net (code "95") (name "Net-(W15-C1)") (class "Default")
      (node (ref "R4") (pin "1") (pinfunction "1_1") (pintype "passive"))
      (node (ref "W15") (pin "1") (pinfunction "C1_1") (pintype "passive"))
    )
  )
)
